# IO_Connectors.net
KiCad netlist of a schematic drawn in Altium Designer
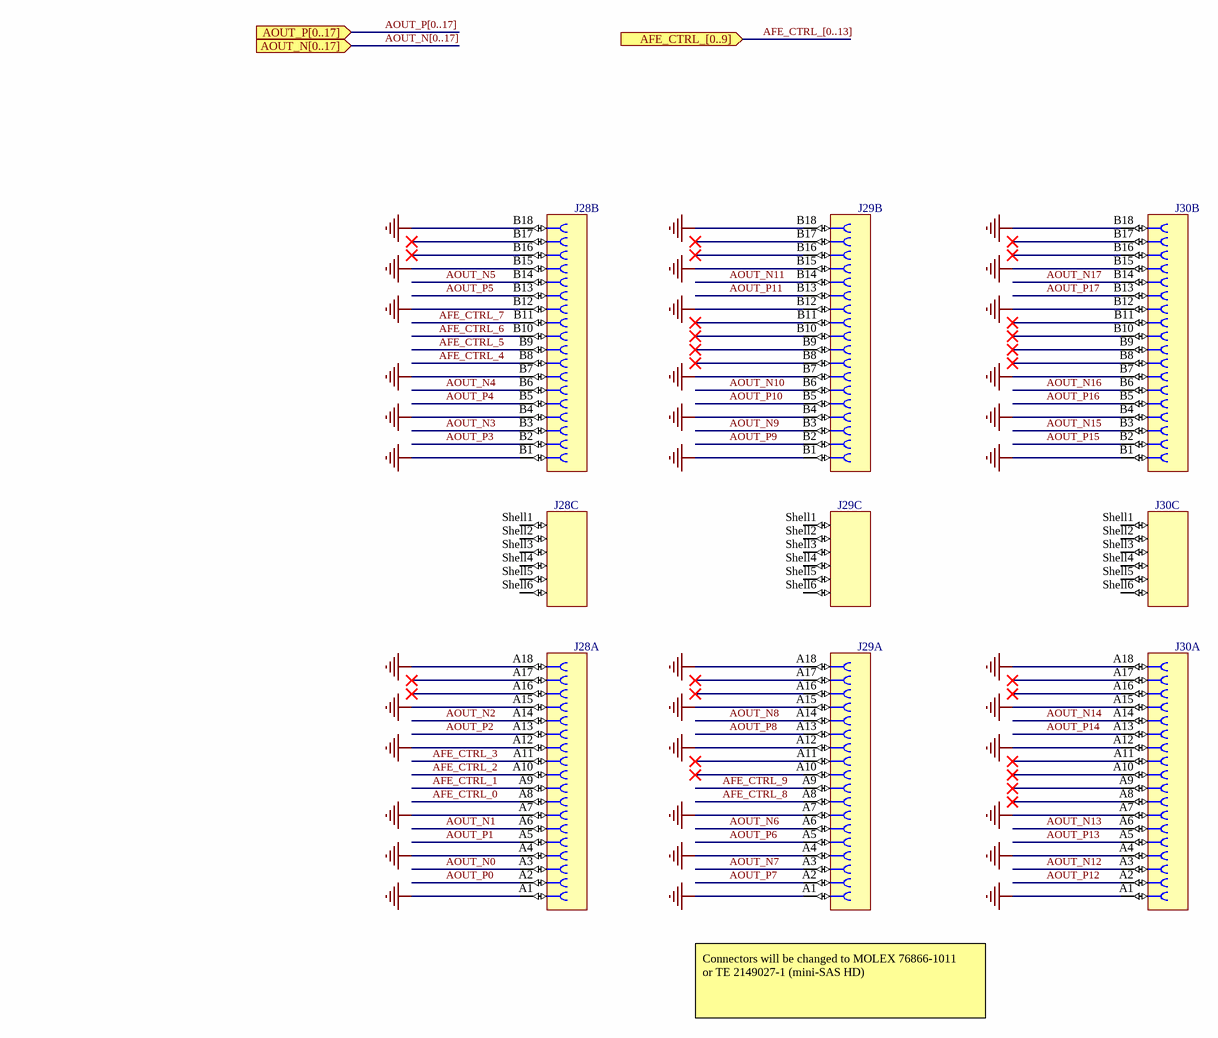
[diagram p0: IO_Connectors.SchDoc]

(export (version "E")
  (design (tool "Eeschema 10.0.6"))
  (components
    (comp (ref "J28")
      (value "iPass™")
      (footprint "MOLEX_75783-0107")
      (fields
        (field (name "PART NUMBER") "MOLEX_75783-0107")
        (field (name "MANUFACTURER") "MOLEX")
        (field (name "MANUFACTURER PART NUMBER") "75783-0107")
        (field (name "AUTHOR") "CERN DEM JLC")
      )
      (libsource (lib "") (part "MOLEX_75783-0107_1"))
    )
    (comp (ref "J29")
      (value "iPass™")
      (footprint "MOLEX_75783-0107")
      (fields
        (field (name "PART NUMBER") "MOLEX_75783-0107")
        (field (name "MANUFACTURER") "MOLEX")
        (field (name "MANUFACTURER PART NUMBER") "75783-0107")
        (field (name "AUTHOR") "CERN DEM JLC")
      )
      (libsource (lib "Connectors") (part "MOLEX_75783-0107"))
    )
    (comp (ref "J30")
      (value "iPass™")
      (footprint "MOLEX_75783-0107")
      (fields
        (field (name "PART NUMBER") "MOLEX_75783-0107")
        (field (name "MANUFACTURER") "MOLEX")
        (field (name "MANUFACTURER PART NUMBER") "75783-0107")
        (field (name "AUTHOR") "CERN DEM JLC")
      )
      (libsource (lib "Connectors") (part "MOLEX_75783-0107"))
    )
  )
  (nets
    (net (code "5") (name "/AFE_CTRL_0") (class "Default")
      (node (ref "J28") (pin "A8") (pinfunction "A8_A8") (pintype "bidirectional"))
    )
    (net (code "6") (name "/AFE_CTRL_1") (class "Default")
      (node (ref "J28") (pin "A9") (pinfunction "A9_A9") (pintype "bidirectional"))
    )
    (net (code "7") (name "/AFE_CTRL_2") (class "Default")
      (node (ref "J28") (pin "A10") (pinfunction "A10_A10") (pintype "bidirectional"))
    )
    (net (code "8") (name "/AFE_CTRL_3") (class "Default")
      (node (ref "J28") (pin "A11") (pinfunction "A11_A11") (pintype "bidirectional"))
    )
    (net (code "9") (name "/AFE_CTRL_4") (class "Default")
      (node (ref "J28") (pin "B8") (pinfunction "B8_B8") (pintype "bidirectional"))
    )
    (net (code "10") (name "/AFE_CTRL_5") (class "Default")
      (node (ref "J28") (pin "B9") (pinfunction "B9_B9") (pintype "bidirectional"))
    )
    (net (code "11") (name "/AFE_CTRL_6") (class "Default")
      (node (ref "J28") (pin "B10") (pinfunction "B10_B10") (pintype "bidirectional"))
    )
    (net (code "12") (name "/AFE_CTRL_7") (class "Default")
      (node (ref "J28") (pin "B11") (pinfunction "B11_B11") (pintype "bidirectional"))
    )
    (net (code "13") (name "/AFE_CTRL_8") (class "Default")
      (node (ref "J29") (pin "A8") (pinfunction "A8_A8") (pintype "bidirectional"))
    )
    (net (code "14") (name "/AFE_CTRL_9") (class "Default")
      (node (ref "J29") (pin "A9") (pinfunction "A9_A9") (pintype "bidirectional"))
    )
    (net (code "16") (name "/AOUT_N0") (class "Default")
      (node (ref "J28") (pin "A3") (pinfunction "A3_A3") (pintype "bidirectional"))
    )
    (net (code "17") (name "/AOUT_N1") (class "Default")
      (node (ref "J28") (pin "A6") (pinfunction "A6_A6") (pintype "bidirectional"))
    )
    (net (code "18") (name "/AOUT_N2") (class "Default")
      (node (ref "J28") (pin "A14") (pinfunction "A14_A14") (pintype "bidirectional"))
    )
    (net (code "19") (name "/AOUT_N3") (class "Default")
      (node (ref "J28") (pin "B3") (pinfunction "B3_B3") (pintype "bidirectional"))
    )
    (net (code "20") (name "/AOUT_N4") (class "Default")
      (node (ref "J28") (pin "B6") (pinfunction "B6_B6") (pintype "bidirectional"))
    )
    (net (code "21") (name "/AOUT_N5") (class "Default")
      (node (ref "J28") (pin "B14") (pinfunction "B14_B14") (pintype "bidirectional"))
    )
    (net (code "22") (name "/AOUT_N6") (class "Default")
      (node (ref "J29") (pin "A6") (pinfunction "A6_A6") (pintype "bidirectional"))
    )
    (net (code "23") (name "/AOUT_N7") (class "Default")
      (node (ref "J29") (pin "A3") (pinfunction "A3_A3") (pintype "bidirectional"))
    )
    (net (code "24") (name "/AOUT_N8") (class "Default")
      (node (ref "J29") (pin "A14") (pinfunction "A14_A14") (pintype "bidirectional"))
    )
    (net (code "25") (name "/AOUT_N9") (class "Default")
      (node (ref "J29") (pin "B3") (pinfunction "B3_B3") (pintype "bidirectional"))
    )
    (net (code "26") (name "/AOUT_N10") (class "Default")
      (node (ref "J29") (pin "B6") (pinfunction "B6_B6") (pintype "bidirectional"))
    )
    (net (code "27") (name "/AOUT_N11") (class "Default")
      (node (ref "J29") (pin "B14") (pinfunction "B14_B14") (pintype "bidirectional"))
    )
    (net (code "28") (name "/AOUT_N12") (class "Default")
      (node (ref "J30") (pin "A3") (pinfunction "A3_A3") (pintype "bidirectional"))
    )
    (net (code "29") (name "/AOUT_N13") (class "Default")
      (node (ref "J30") (pin "A6") (pinfunction "A6_A6") (pintype "bidirectional"))
    )
    (net (code "30") (name "/AOUT_N14") (class "Default")
      (node (ref "J30") (pin "A14") (pinfunction "A14_A14") (pintype "bidirectional"))
    )
    (net (code "31") (name "/AOUT_N15") (class "Default")
      (node (ref "J30") (pin "B3") (pinfunction "B3_B3") (pintype "bidirectional"))
    )
    (net (code "32") (name "/AOUT_N16") (class "Default")
      (node (ref "J30") (pin "B6") (pinfunction "B6_B6") (pintype "bidirectional"))
    )
    (net (code "33") (name "/AOUT_N17") (class "Default")
      (node (ref "J30") (pin "B14") (pinfunction "B14_B14") (pintype "bidirectional"))
    )
    (net (code "35") (name "/AOUT_P0") (class "Default")
      (node (ref "J28") (pin "A2") (pinfunction "A2_A2") (pintype "bidirectional"))
    )
    (net (code "36") (name "/AOUT_P1") (class "Default")
      (node (ref "J28") (pin "A5") (pinfunction "A5_A5") (pintype "bidirectional"))
    )
    (net (code "37") (name "/AOUT_P2") (class "Default")
      (node (ref "J28") (pin "A13") (pinfunction "A13_A13") (pintype "bidirectional"))
    )
    (net (code "38") (name "/AOUT_P3") (class "Default")
      (node (ref "J28") (pin "B2") (pinfunction "B2_B2") (pintype "bidirectional"))
    )
    (net (code "39") (name "/AOUT_P4") (class "Default")
      (node (ref "J28") (pin "B5") (pinfunction "B5_B5") (pintype "bidirectional"))
    )
    (net (code "40") (name "/AOUT_P5") (class "Default")
      (node (ref "J28") (pin "B13") (pinfunction "B13_B13") (pintype "bidirectional"))
    )
    (net (code "41") (name "/AOUT_P6") (class "Default")
      (node (ref "J29") (pin "A5") (pinfunction "A5_A5") (pintype "bidirectional"))
    )
    (net (code "42") (name "/AOUT_P7") (class "Default")
      (node (ref "J29") (pin "A2") (pinfunction "A2_A2") (pintype "bidirectional"))
    )
    (net (code "43") (name "/AOUT_P8") (class "Default")
      (node (ref "J29") (pin "A13") (pinfunction "A13_A13") (pintype "bidirectional"))
    )
    (net (code "44") (name "/AOUT_P9") (class "Default")
      (node (ref "J29") (pin "B2") (pinfunction "B2_B2") (pintype "bidirectional"))
    )
    (net (code "45") (name "/AOUT_P10") (class "Default")
      (node (ref "J29") (pin "B5") (pinfunction "B5_B5") (pintype "bidirectional"))
    )
    (net (code "46") (name "/AOUT_P11") (class "Default")
      (node (ref "J29") (pin "B13") (pinfunction "B13_B13") (pintype "bidirectional"))
    )
    (net (code "47") (name "/AOUT_P12") (class "Default")
      (node (ref "J30") (pin "A2") (pinfunction "A2_A2") (pintype "bidirectional"))
    )
    (net (code "48") (name "/AOUT_P13") (class "Default")
      (node (ref "J30") (pin "A5") (pinfunction "A5_A5") (pintype "bidirectional"))
    )
    (net (code "49") (name "/AOUT_P14") (class "Default")
      (node (ref "J30") (pin "A13") (pinfunction "A13_A13") (pintype "bidirectional"))
    )
    (net (code "50") (name "/AOUT_P15") (class "Default")
      (node (ref "J30") (pin "B2") (pinfunction "B2_B2") (pintype "bidirectional"))
    )
    (net (code "51") (name "/AOUT_P16") (class "Default")
      (node (ref "J30") (pin "B5") (pinfunction "B5_B5") (pintype "bidirectional"))
    )
    (net (code "52") (name "/AOUT_P17") (class "Default")
      (node (ref "J30") (pin "B13") (pinfunction "B13_B13") (pintype "bidirectional"))
    )
    (net (code "54") (name "GND") (class "Default")
      (node (ref "J28") (pin "A1") (pinfunction "A1_A1") (pintype "bidirectional"))
      (node (ref "J28") (pin "A12") (pinfunction "A12_A12") (pintype "bidirectional"))
      (node (ref "J28") (pin "A15") (pinfunction "A15_A15") (pintype "bidirectional"))
      (node (ref "J28") (pin "A18") (pinfunction "A18_A18") (pintype "bidirectional"))
      (node (ref "J28") (pin "A4") (pinfunction "A4_A4") (pintype "bidirectional"))
      (node (ref "J28") (pin "A7") (pinfunction "A7_A7") (pintype "bidirectional"))
      (node (ref "J28") (pin "B1") (pinfunction "B1_B1") (pintype "bidirectional"))
      (node (ref "J28") (pin "B12") (pinfunction "B12_B12") (pintype "bidirectional"))
      (node (ref "J28") (pin "B15") (pinfunction "B15_B15") (pintype "bidirectional"))
      (node (ref "J28") (pin "B18") (pinfunction "B18_B18") (pintype "bidirectional"))
      (node (ref "J28") (pin "B4") (pinfunction "B4_B4") (pintype "bidirectional"))
      (node (ref "J28") (pin "B7") (pinfunction "B7_B7") (pintype "bidirectional"))
      (node (ref "J29") (pin "A1") (pinfunction "A1_A1") (pintype "bidirectional"))
      (node (ref "J29") (pin "A12") (pinfunction "A12_A12") (pintype "bidirectional"))
      (node (ref "J29") (pin "A15") (pinfunction "A15_A15") (pintype "bidirectional"))
      (node (ref "J29") (pin "A18") (pinfunction "A18_A18") (pintype "bidirectional"))
      (node (ref "J29") (pin "A4") (pinfunction "A4_A4") (pintype "bidirectional"))
      (node (ref "J29") (pin "A7") (pinfunction "A7_A7") (pintype "bidirectional"))
      (node (ref "J29") (pin "B1") (pinfunction "B1_B1") (pintype "bidirectional"))
      (node (ref "J29") (pin "B12") (pinfunction "B12_B12") (pintype "bidirectional"))
      (node (ref "J29") (pin "B15") (pinfunction "B15_B15") (pintype "bidirectional"))
      (node (ref "J29") (pin "B18") (pinfunction "B18_B18") (pintype "bidirectional"))
      (node (ref "J29") (pin "B4") (pinfunction "B4_B4") (pintype "bidirectional"))
      (node (ref "J29") (pin "B7") (pinfunction "B7_B7") (pintype "bidirectional"))
      (node (ref "J30") (pin "A1") (pinfunction "A1_A1") (pintype "bidirectional"))
      (node (ref "J30") (pin "A12") (pinfunction "A12_A12") (pintype "bidirectional"))
      (node (ref "J30") (pin "A15") (pinfunction "A15_A15") (pintype "bidirectional"))
      (node (ref "J30") (pin "A18") (pinfunction "A18_A18") (pintype "bidirectional"))
      (node (ref "J30") (pin "A4") (pinfunction "A4_A4") (pintype "bidirectional"))
      (node (ref "J30") (pin "A7") (pinfunction "A7_A7") (pintype "bidirectional"))
      (node (ref "J30") (pin "B1") (pinfunction "B1_B1") (pintype "bidirectional"))
      (node (ref "J30") (pin "B12") (pinfunction "B12_B12") (pintype "bidirectional"))
      (node (ref "J30") (pin "B15") (pinfunction "B15_B15") (pintype "bidirectional"))
      (node (ref "J30") (pin "B18") (pinfunction "B18_B18") (pintype "bidirectional"))
      (node (ref "J30") (pin "B4") (pinfunction "B4_B4") (pintype "bidirectional"))
      (node (ref "J30") (pin "B7") (pinfunction "B7_B7") (pintype "bidirectional"))
    )
    (net (code "55") (name "unconnected-(J28-PadA16)") (class "Default")
      (node (ref "J28") (pin "A16") (pinfunction "A16_A16") (pintype "bidirectional+no_connect"))
    )
    (net (code "56") (name "unconnected-(J28-PadA17)") (class "Default")
      (node (ref "J28") (pin "A17") (pinfunction "A17_A17") (pintype "bidirectional+no_connect"))
    )
    (net (code "57") (name "unconnected-(J28-PadB16)") (class "Default")
      (node (ref "J28") (pin "B16") (pinfunction "B16_B16") (pintype "bidirectional+no_connect"))
    )
    (net (code "58") (name "unconnected-(J28-PadB17)") (class "Default")
      (node (ref "J28") (pin "B17") (pinfunction "B17_B17") (pintype "bidirectional+no_connect"))
    )
    (net (code "59") (name "unconnected-(J28-PadShell1)") (class "Default")
      (node (ref "J28") (pin "Shell1") (pinfunction "Shell1_Shell1") (pintype "bidirectional"))
    )
    (net (code "60") (name "unconnected-(J28-PadShell2)") (class "Default")
      (node (ref "J28") (pin "Shell2") (pinfunction "Shell2_Shell2") (pintype "bidirectional"))
    )
    (net (code "61") (name "unconnected-(J28-PadShell3)") (class "Default")
      (node (ref "J28") (pin "Shell3") (pinfunction "Shell3_Shell3") (pintype "bidirectional"))
    )
    (net (code "62") (name "unconnected-(J28-PadShell4)") (class "Default")
      (node (ref "J28") (pin "Shell4") (pinfunction "Shell4_Shell4") (pintype "bidirectional"))
    )
    (net (code "63") (name "unconnected-(J28-PadShell5)") (class "Default")
      (node (ref "J28") (pin "Shell5") (pinfunction "Shell5_Shell5") (pintype "bidirectional"))
    )
    (net (code "64") (name "unconnected-(J28-PadShell6)") (class "Default")
      (node (ref "J28") (pin "Shell6") (pinfunction "Shell6_Shell6") (pintype "bidirectional"))
    )
    (net (code "65") (name "unconnected-(J29-PadA10)") (class "Default")
      (node (ref "J29") (pin "A10") (pinfunction "A10_A10") (pintype "bidirectional+no_connect"))
    )
    (net (code "66") (name "unconnected-(J29-PadA11)") (class "Default")
      (node (ref "J29") (pin "A11") (pinfunction "A11_A11") (pintype "bidirectional+no_connect"))
    )
    (net (code "67") (name "unconnected-(J29-PadA16)") (class "Default")
      (node (ref "J29") (pin "A16") (pinfunction "A16_A16") (pintype "bidirectional+no_connect"))
    )
    (net (code "68") (name "unconnected-(J29-PadA17)") (class "Default")
      (node (ref "J29") (pin "A17") (pinfunction "A17_A17") (pintype "bidirectional+no_connect"))
    )
    (net (code "69") (name "unconnected-(J29-PadB8)") (class "Default")
      (node (ref "J29") (pin "B8") (pinfunction "B8_B8") (pintype "bidirectional+no_connect"))
    )
    (net (code "70") (name "unconnected-(J29-PadB9)") (class "Default")
      (node (ref "J29") (pin "B9") (pinfunction "B9_B9") (pintype "bidirectional+no_connect"))
    )
    (net (code "71") (name "unconnected-(J29-PadB10)") (class "Default")
      (node (ref "J29") (pin "B10") (pinfunction "B10_B10") (pintype "bidirectional+no_connect"))
    )
    (net (code "72") (name "unconnected-(J29-PadB11)") (class "Default")
      (node (ref "J29") (pin "B11") (pinfunction "B11_B11") (pintype "bidirectional+no_connect"))
    )
    (net (code "73") (name "unconnected-(J29-PadB16)") (class "Default")
      (node (ref "J29") (pin "B16") (pinfunction "B16_B16") (pintype "bidirectional+no_connect"))
    )
    (net (code "74") (name "unconnected-(J29-PadB17)") (class "Default")
      (node (ref "J29") (pin "B17") (pinfunction "B17_B17") (pintype "bidirectional+no_connect"))
    )
    (net (code "75") (name "unconnected-(J29-PadShell1)") (class "Default")
      (node (ref "J29") (pin "Shell1") (pinfunction "Shell1_Shell1") (pintype "bidirectional"))
    )
    (net (code "76") (name "unconnected-(J29-PadShell2)") (class "Default")
      (node (ref "J29") (pin "Shell2") (pinfunction "Shell2_Shell2") (pintype "bidirectional"))
    )
    (net (code "77") (name "unconnected-(J29-PadShell3)") (class "Default")
      (node (ref "J29") (pin "Shell3") (pinfunction "Shell3_Shell3") (pintype "bidirectional"))
    )
    (net (code "78") (name "unconnected-(J29-PadShell4)") (class "Default")
      (node (ref "J29") (pin "Shell4") (pinfunction "Shell4_Shell4") (pintype "bidirectional"))
    )
    (net (code "79") (name "unconnected-(J29-PadShell5)") (class "Default")
      (node (ref "J29") (pin "Shell5") (pinfunction "Shell5_Shell5") (pintype "bidirectional"))
    )
    (net (code "80") (name "unconnected-(J29-PadShell6)") (class "Default")
      (node (ref "J29") (pin "Shell6") (pinfunction "Shell6_Shell6") (pintype "bidirectional"))
    )
    (net (code "81") (name "unconnected-(J30-PadA8)") (class "Default")
      (node (ref "J30") (pin "A8") (pinfunction "A8_A8") (pintype "bidirectional+no_connect"))
    )
    (net (code "82") (name "unconnected-(J30-PadA9)") (class "Default")
      (node (ref "J30") (pin "A9") (pinfunction "A9_A9") (pintype "bidirectional+no_connect"))
    )
    (net (code "83") (name "unconnected-(J30-PadA10)") (class "Default")
      (node (ref "J30") (pin "A10") (pinfunction "A10_A10") (pintype "bidirectional+no_connect"))
    )
    (net (code "84") (name "unconnected-(J30-PadA11)") (class "Default")
      (node (ref "J30") (pin "A11") (pinfunction "A11_A11") (pintype "bidirectional+no_connect"))
    )
    (net (code "85") (name "unconnected-(J30-PadA16)") (class "Default")
      (node (ref "J30") (pin "A16") (pinfunction "A16_A16") (pintype "bidirectional+no_connect"))
    )
    (net (code "86") (name "unconnected-(J30-PadA17)") (class "Default")
      (node (ref "J30") (pin "A17") (pinfunction "A17_A17") (pintype "bidirectional+no_connect"))
    )
    (net (code "87") (name "unconnected-(J30-PadB8)") (class "Default")
      (node (ref "J30") (pin "B8") (pinfunction "B8_B8") (pintype "bidirectional+no_connect"))
    )
    (net (code "88") (name "unconnected-(J30-PadB9)") (class "Default")
      (node (ref "J30") (pin "B9") (pinfunction "B9_B9") (pintype "bidirectional+no_connect"))
    )
    (net (code "89") (name "unconnected-(J30-PadB10)") (class "Default")
      (node (ref "J30") (pin "B10") (pinfunction "B10_B10") (pintype "bidirectional+no_connect"))
    )
    (net (code "90") (name "unconnected-(J30-PadB11)") (class "Default")
      (node (ref "J30") (pin "B11") (pinfunction "B11_B11") (pintype "bidirectional+no_connect"))
    )
    (net (code "91") (name "unconnected-(J30-PadB16)") (class "Default")
      (node (ref "J30") (pin "B16") (pinfunction "B16_B16") (pintype "bidirectional+no_connect"))
    )
    (net (code "92") (name "unconnected-(J30-PadB17)") (class "Default")
      (node (ref "J30") (pin "B17") (pinfunction "B17_B17") (pintype "bidirectional+no_connect"))
    )
    (net (code "93") (name "unconnected-(J30-PadShell1)") (class "Default")
      (node (ref "J30") (pin "Shell1") (pinfunction "Shell1_Shell1") (pintype "bidirectional"))
    )
    (net (code "94") (name "unconnected-(J30-PadShell2)") (class "Default")
      (node (ref "J30") (pin "Shell2") (pinfunction "Shell2_Shell2") (pintype "bidirectional"))
    )
    (net (code "95") (name "unconnected-(J30-PadShell3)") (class "Default")
      (node (ref "J30") (pin "Shell3") (pinfunction "Shell3_Shell3") (pintype "bidirectional"))
    )
    (net (code "96") (name "unconnected-(J30-PadShell4)") (class "Default")
      (node (ref "J30") (pin "Shell4") (pinfunction "Shell4_Shell4") (pintype "bidirectional"))
    )
    (net (code "97") (name "unconnected-(J30-PadShell5)") (class "Default")
      (node (ref "J30") (pin "Shell5") (pinfunction "Shell5_Shell5") (pintype "bidirectional"))
    )
    (net (code "98") (name "unconnected-(J30-PadShell6)") (class "Default")
      (node (ref "J30") (pin "Shell6") (pinfunction "Shell6_Shell6") (pintype "bidirectional"))
    )
  )
)
